# Power.net
KiCad netlist of a schematic drawn in Altium Designer
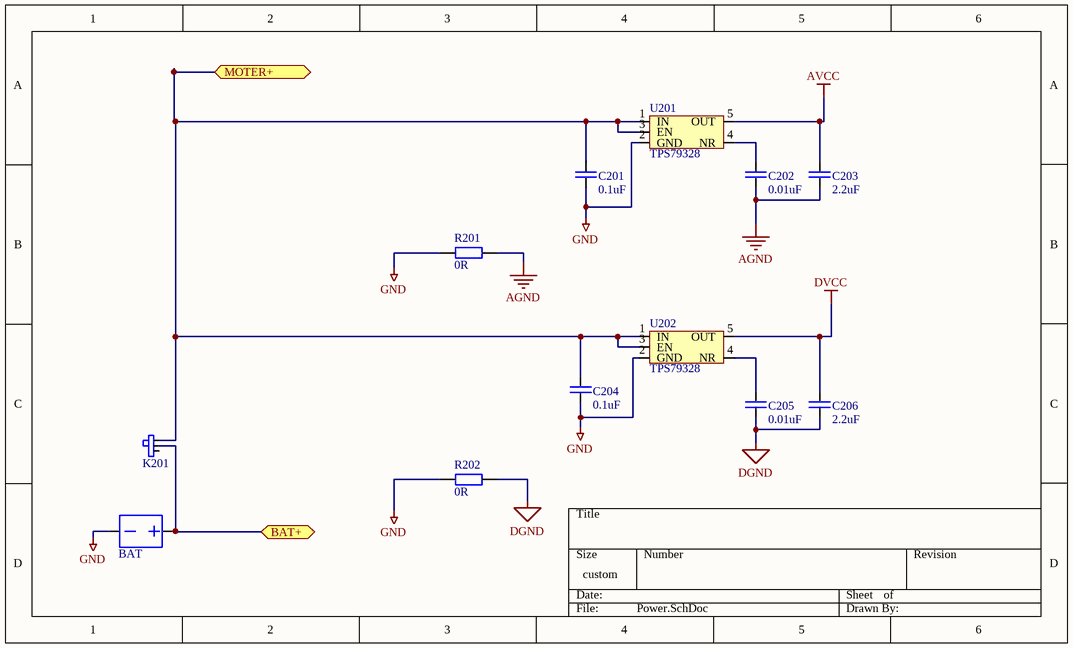
[diagram p0: Power.SchDoc]

(export (version "E")
  (design (tool "Eeschema 10.0.6"))
  (components
    (comp (ref "BAT") (value "BAT") (footprint "XH254") (libsource (lib "Library") (part "BAT")))
    (comp (ref "C201") (value "0.1uF") (footprint "0603") (libsource (lib "Library") (part "C0603")))
    (comp (ref "C202") (value "0.01uF") (footprint "0603") (libsource (lib "Library") (part "C0603")))
    (comp (ref "C203") (value "2.2uF") (footprint "0603") (libsource (lib "Library") (part "C0603")))
    (comp (ref "C204") (value "0.1uF") (footprint "0603") (libsource (lib "Library") (part "C0603")))
    (comp (ref "C205") (value "0.01uF") (footprint "0603") (libsource (lib "Library") (part "C0603")))
    (comp (ref "C206") (value "2.2uF") (footprint "0603") (libsource (lib "Library") (part "C0603")))
    (comp (ref "K201") (value "32开关") (footprint "32k") (libsource (lib "Library") (part "32开关")))
    (comp (ref "R201") (value "0R") (footprint "0603") (libsource (lib "Library") (part "R0603")))
    (comp (ref "R202") (value "0R") (footprint "0603") (libsource (lib "Library") (part "R0603")))
    (comp (ref "U201")
      (value "TPS79328")
      (footprint "TPS793xx")
      (libsource (lib "Library") (part "TPS793xx"))
    )
    (comp (ref "U202")
      (value "TPS79328")
      (footprint "TPS793xx")
      (libsource (lib "Library") (part "TPS793xx"))
    )
  )
  (nets
    (net (code "1") (name "/BAT+") (class "Default")
      (node (ref "BAT") (pin "2") (pinfunction "2_2") (pintype "passive"))
      (node (ref "K201") (pin "2") (pinfunction "2_2") (pintype "passive"))
    )
    (net (code "2") (name "/MOTER+") (class "Default")
      (node (ref "C201") (pin "2") (pinfunction "2_2") (pintype "passive"))
      (node (ref "C204") (pin "2") (pinfunction "2_2") (pintype "passive"))
      (node (ref "K201") (pin "1") (pinfunction "1_1") (pintype "passive"))
      (node (ref "U201") (pin "1") (pinfunction "IN_1") (pintype "passive"))
      (node (ref "U201") (pin "3") (pinfunction "EN_3") (pintype "passive"))
      (node (ref "U202") (pin "1") (pinfunction "IN_1") (pintype "passive"))
      (node (ref "U202") (pin "3") (pinfunction "EN_3") (pintype "passive"))
    )
    (net (code "3") (name "AGND") (class "Default")
      (node (ref "C202") (pin "1") (pinfunction "1_1") (pintype "passive"))
      (node (ref "C203") (pin "1") (pinfunction "1_1") (pintype "passive"))
      (node (ref "R201") (pin "1") (pinfunction "1_1") (pintype "passive"))
    )
    (net (code "4") (name "AVCC") (class "Default")
      (node (ref "C203") (pin "2") (pinfunction "2_2") (pintype "passive"))
      (node (ref "U201") (pin "5") (pinfunction "OUT_5") (pintype "passive"))
    )
    (net (code "5") (name "DGND") (class "Default")
      (node (ref "C205") (pin "1") (pinfunction "1_1") (pintype "passive"))
      (node (ref "C206") (pin "1") (pinfunction "1_1") (pintype "passive"))
      (node (ref "R202") (pin "1") (pinfunction "1_1") (pintype "passive"))
    )
    (net (code "6") (name "DVCC") (class "Default")
      (node (ref "C206") (pin "2") (pinfunction "2_2") (pintype "passive"))
      (node (ref "U202") (pin "5") (pinfunction "OUT_5") (pintype "passive"))
    )
    (net (code "7") (name "GND") (class "Default")
      (node (ref "BAT") (pin "1") (pinfunction "1_1") (pintype "passive"))
      (node (ref "C201") (pin "1") (pinfunction "1_1") (pintype "passive"))
      (node (ref "C204") (pin "1") (pinfunction "1_1") (pintype "passive"))
      (node (ref "R201") (pin "2") (pinfunction "2_2") (pintype "passive"))
      (node (ref "R202") (pin "2") (pinfunction "2_2") (pintype "passive"))
      (node (ref "U201") (pin "2") (pinfunction "GND_2") (pintype "passive"))
      (node (ref "U202") (pin "2") (pinfunction "GND_2") (pintype "passive"))
    )
    (net (code "8") (name "Net-(U201-NR)") (class "Default")
      (node (ref "C202") (pin "2") (pinfunction "2_2") (pintype "passive"))
      (node (ref "U201") (pin "4") (pinfunction "NR_4") (pintype "passive"))
    )
    (net (code "9") (name "Net-(U202-NR)") (class "Default")
      (node (ref "C205") (pin "2") (pinfunction "2_2") (pintype "passive"))
      (node (ref "U202") (pin "4") (pinfunction "NR_4") (pintype "passive"))
    )
    (net (code "10") (name "unconnected-(K201-Pad3)") (class "Default")
      (node (ref "K201") (pin "3") (pinfunction "3_3") (pintype "passive"))
    )
  )
)
